# WHITE_LINE_FINAL_1.net
KiCad netlist of a schematic drawn in EAGLE
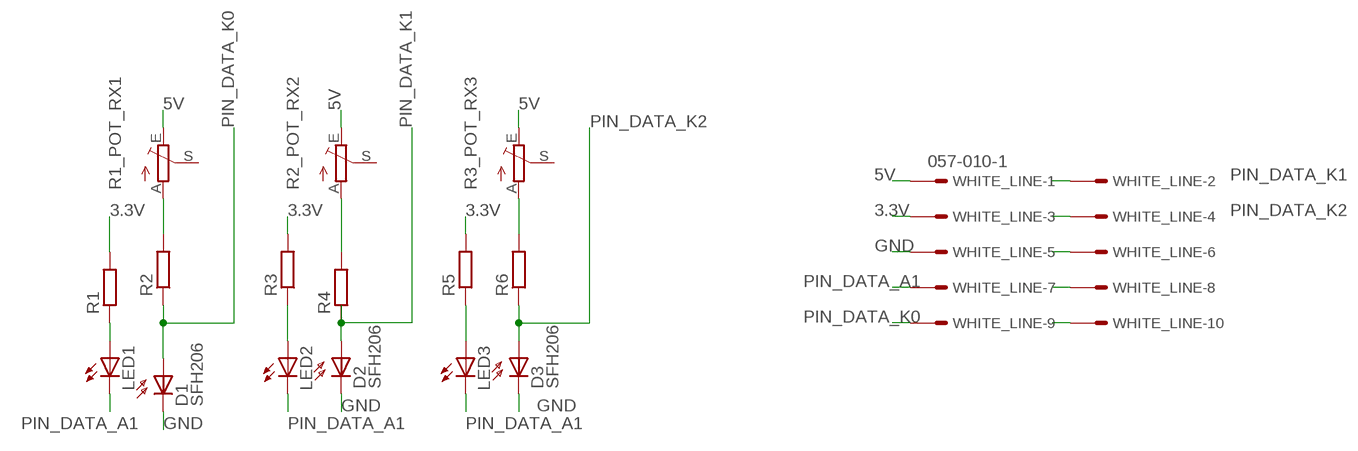
[diagram p0: schematic, sheet 1]

(export (version "E")
  (design (tool "Eeschema 10.0.6"))
  (components
    (comp (ref "D1")
      (value "SFH206")
      (footprint "eagle-import:SFH206")
      (fields (field (name "MPN") "SFH206K"))
      (libsource (lib "eagle-import") (part "SFH206"))
    )
    (comp (ref "D2")
      (value "SFH206")
      (footprint "eagle-import:SFH206")
      (fields (field (name "MPN") "SFH206K"))
      (libsource (lib "eagle-import") (part "SFH206"))
    )
    (comp (ref "D3")
      (value "SFH206")
      (footprint "eagle-import:SFH206")
      (fields (field (name "MPN") "SFH206K"))
      (libsource (lib "eagle-import") (part "SFH206"))
    )
    (comp (ref "LED1")
      (value "LED-2AC-CP41B-WES")
      (footprint "eagle-import:CP41B")
      (libsource (lib "eagle-import") (part "LED-2AC-CP41B-WES"))
    )
    (comp (ref "LED2")
      (value "LED-2AC-CP41B-WES")
      (footprint "eagle-import:CP41B")
      (libsource (lib "eagle-import") (part "LED-2AC-CP41B-WES"))
    )
    (comp (ref "LED3")
      (value "LED-2AC-CP41B-WES")
      (footprint "eagle-import:CP41B")
      (libsource (lib "eagle-import") (part "LED-2AC-CP41B-WES"))
    )
    (comp (ref "R1")
      (value "R-EU_M1206")
      (footprint "eagle-import:M1206")
      (libsource (lib "eagle-import") (part "R-EU_M1206"))
    )
    (comp (ref "R1_POT_RX1")
      (value "TRIM_EU-CA6V")
      (footprint "eagle-import:CA6V")
      (libsource (lib "eagle-import") (part "TRIM_EU-CA6V"))
    )
    (comp (ref "R2")
      (value "R-EU_M1206")
      (footprint "eagle-import:M1206")
      (libsource (lib "eagle-import") (part "R-EU_M1206"))
    )
    (comp (ref "R2_POT_RX2")
      (value "TRIM_EU-CA6V")
      (footprint "eagle-import:CA6V")
      (libsource (lib "eagle-import") (part "TRIM_EU-CA6V"))
    )
    (comp (ref "R3")
      (value "R-EU_M1206")
      (footprint "eagle-import:M1206")
      (libsource (lib "eagle-import") (part "R-EU_M1206"))
    )
    (comp (ref "R3_POT_RX3")
      (value "TRIM_EU-CA6V")
      (footprint "eagle-import:CA6V")
      (libsource (lib "eagle-import") (part "TRIM_EU-CA6V"))
    )
    (comp (ref "R4")
      (value "R-EU_M1206")
      (footprint "eagle-import:M1206")
      (libsource (lib "eagle-import") (part "R-EU_M1206"))
    )
    (comp (ref "R5")
      (value "R-EU_M1206")
      (footprint "eagle-import:M1206")
      (libsource (lib "eagle-import") (part "R-EU_M1206"))
    )
    (comp (ref "R6")
      (value "R-EU_M1206")
      (footprint "eagle-import:M1206")
      (libsource (lib "eagle-import") (part "R-EU_M1206"))
    )
    (comp (ref "WHITE_LINE")
      (value "057-010-1")
      (footprint "eagle-import:057-010-1")
      (libsource (lib "eagle-import") (part "057-010-1"))
    )
  )
  (nets
    (net (code "1") (name "/3.3V") (class "Default")
      (node (ref "R1") (pin "2") (pinfunction "2_2") (pintype "passive"))
      (node (ref "R3") (pin "2") (pinfunction "2_2") (pintype "passive"))
      (node (ref "R5") (pin "2") (pinfunction "2_2") (pintype "passive"))
      (node (ref "WHITE_LINE") (pin "3") (pinfunction "S_3") (pintype "passive"))
    )
    (net (code "2") (name "/5V") (class "Default")
      (node (ref "R1_POT_RX1") (pin "E") (pinfunction "E_E") (pintype "passive"))
      (node (ref "R2_POT_RX2") (pin "E") (pinfunction "E_E") (pintype "passive"))
      (node (ref "R3_POT_RX3") (pin "E") (pinfunction "E_E") (pintype "passive"))
      (node (ref "WHITE_LINE") (pin "1") (pinfunction "S_1") (pintype "passive"))
    )
    (net (code "3") (name "/GND") (class "Default")
      (node (ref "D1") (pin "K") (pinfunction "C_K") (pintype "passive"))
      (node (ref "D2") (pin "K") (pinfunction "C_K") (pintype "passive"))
      (node (ref "D3") (pin "K") (pinfunction "C_K") (pintype "passive"))
      (node (ref "WHITE_LINE") (pin "5") (pinfunction "S_5") (pintype "passive"))
    )
    (net (code "4") (name "/PIN_DATA_A1") (class "Default")
      (node (ref "LED1") (pin "1") (pinfunction "C_1") (pintype "passive"))
      (node (ref "LED1") (pin "4") (pinfunction "C_4") (pintype "passive"))
      (node (ref "LED2") (pin "1") (pinfunction "C_1") (pintype "passive"))
      (node (ref "LED2") (pin "4") (pinfunction "C_4") (pintype "passive"))
      (node (ref "LED3") (pin "1") (pinfunction "C_1") (pintype "passive"))
      (node (ref "LED3") (pin "4") (pinfunction "C_4") (pintype "passive"))
      (node (ref "WHITE_LINE") (pin "7") (pinfunction "S_7") (pintype "passive"))
    )
    (net (code "5") (name "/PIN_DATA_K0") (class "Default")
      (node (ref "D1") (pin "A") (pinfunction "A_A") (pintype "passive"))
      (node (ref "R2") (pin "1") (pinfunction "1_1") (pintype "passive"))
      (node (ref "WHITE_LINE") (pin "9") (pinfunction "S_9") (pintype "passive"))
    )
    (net (code "6") (name "/PIN_DATA_K1") (class "Default")
      (node (ref "D2") (pin "A") (pinfunction "A_A") (pintype "passive"))
      (node (ref "R4") (pin "1") (pinfunction "1_1") (pintype "passive"))
      (node (ref "WHITE_LINE") (pin "2") (pinfunction "S_2") (pintype "passive"))
    )
    (net (code "7") (name "/PIN_DATA_K2") (class "Default")
      (node (ref "D3") (pin "A") (pinfunction "A_A") (pintype "passive"))
      (node (ref "R6") (pin "1") (pinfunction "1_1") (pintype "passive"))
      (node (ref "WHITE_LINE") (pin "4") (pinfunction "S_4") (pintype "passive"))
    )
    (net (code "8") (name "Net-(LED1-A-Pad2)") (class "Default")
      (node (ref "LED1") (pin "2") (pinfunction "A_2") (pintype "passive"))
      (node (ref "LED1") (pin "3") (pinfunction "A_3") (pintype "passive"))
      (node (ref "R1") (pin "1") (pinfunction "1_1") (pintype "passive"))
    )
    (net (code "9") (name "Net-(LED2-A-Pad2)") (class "Default")
      (node (ref "LED2") (pin "2") (pinfunction "A_2") (pintype "passive"))
      (node (ref "LED2") (pin "3") (pinfunction "A_3") (pintype "passive"))
      (node (ref "R3") (pin "1") (pinfunction "1_1") (pintype "passive"))
    )
    (net (code "10") (name "Net-(LED3-A-Pad2)") (class "Default")
      (node (ref "LED3") (pin "2") (pinfunction "A_2") (pintype "passive"))
      (node (ref "LED3") (pin "3") (pinfunction "A_3") (pintype "passive"))
      (node (ref "R5") (pin "1") (pinfunction "1_1") (pintype "passive"))
    )
    (net (code "11") (name "Net-(R1_POT_RX1-PadA)") (class "Default")
      (node (ref "R1_POT_RX1") (pin "A") (pinfunction "A_A") (pintype "passive"))
      (node (ref "R2") (pin "2") (pinfunction "2_2") (pintype "passive"))
    )
    (net (code "12") (name "Net-(R2_POT_RX2-PadA)") (class "Default")
      (node (ref "R2_POT_RX2") (pin "A") (pinfunction "A_A") (pintype "passive"))
      (node (ref "R4") (pin "2") (pinfunction "2_2") (pintype "passive"))
    )
    (net (code "13") (name "Net-(R3_POT_RX3-PadA)") (class "Default")
      (node (ref "R3_POT_RX3") (pin "A") (pinfunction "A_A") (pintype "passive"))
      (node (ref "R6") (pin "2") (pinfunction "2_2") (pintype "passive"))
    )
    (net (code "14") (name "unconnected-(R1_POT_RX1-PadS)") (class "Default")
      (node (ref "R1_POT_RX1") (pin "S") (pinfunction "S_S") (pintype "passive"))
    )
    (net (code "15") (name "unconnected-(R2_POT_RX2-PadS)") (class "Default")
      (node (ref "R2_POT_RX2") (pin "S") (pinfunction "S_S") (pintype "passive"))
    )
    (net (code "16") (name "unconnected-(R3_POT_RX3-PadS)") (class "Default")
      (node (ref "R3_POT_RX3") (pin "S") (pinfunction "S_S") (pintype "passive"))
    )
    (net (code "17") (name "unconnected-(WHITE_LINEB-S-Pad10)") (class "Default")
      (node (ref "WHITE_LINE") (pin "10") (pinfunction "S_10") (pintype "passive"))
    )
    (net (code "18") (name "unconnected-(WHITE_LINEG-S-Pad6)") (class "Default")
      (node (ref "WHITE_LINE") (pin "6") (pinfunction "S_6") (pintype "passive"))
    )
    (net (code "19") (name "unconnected-(WHITE_LINEI-S-Pad8)") (class "Default")
      (node (ref "WHITE_LINE") (pin "8") (pinfunction "S_8") (pintype "passive"))
    )
  )
)
